# PowerCircuitry.net
KiCad netlist of a schematic drawn in Altium Designer
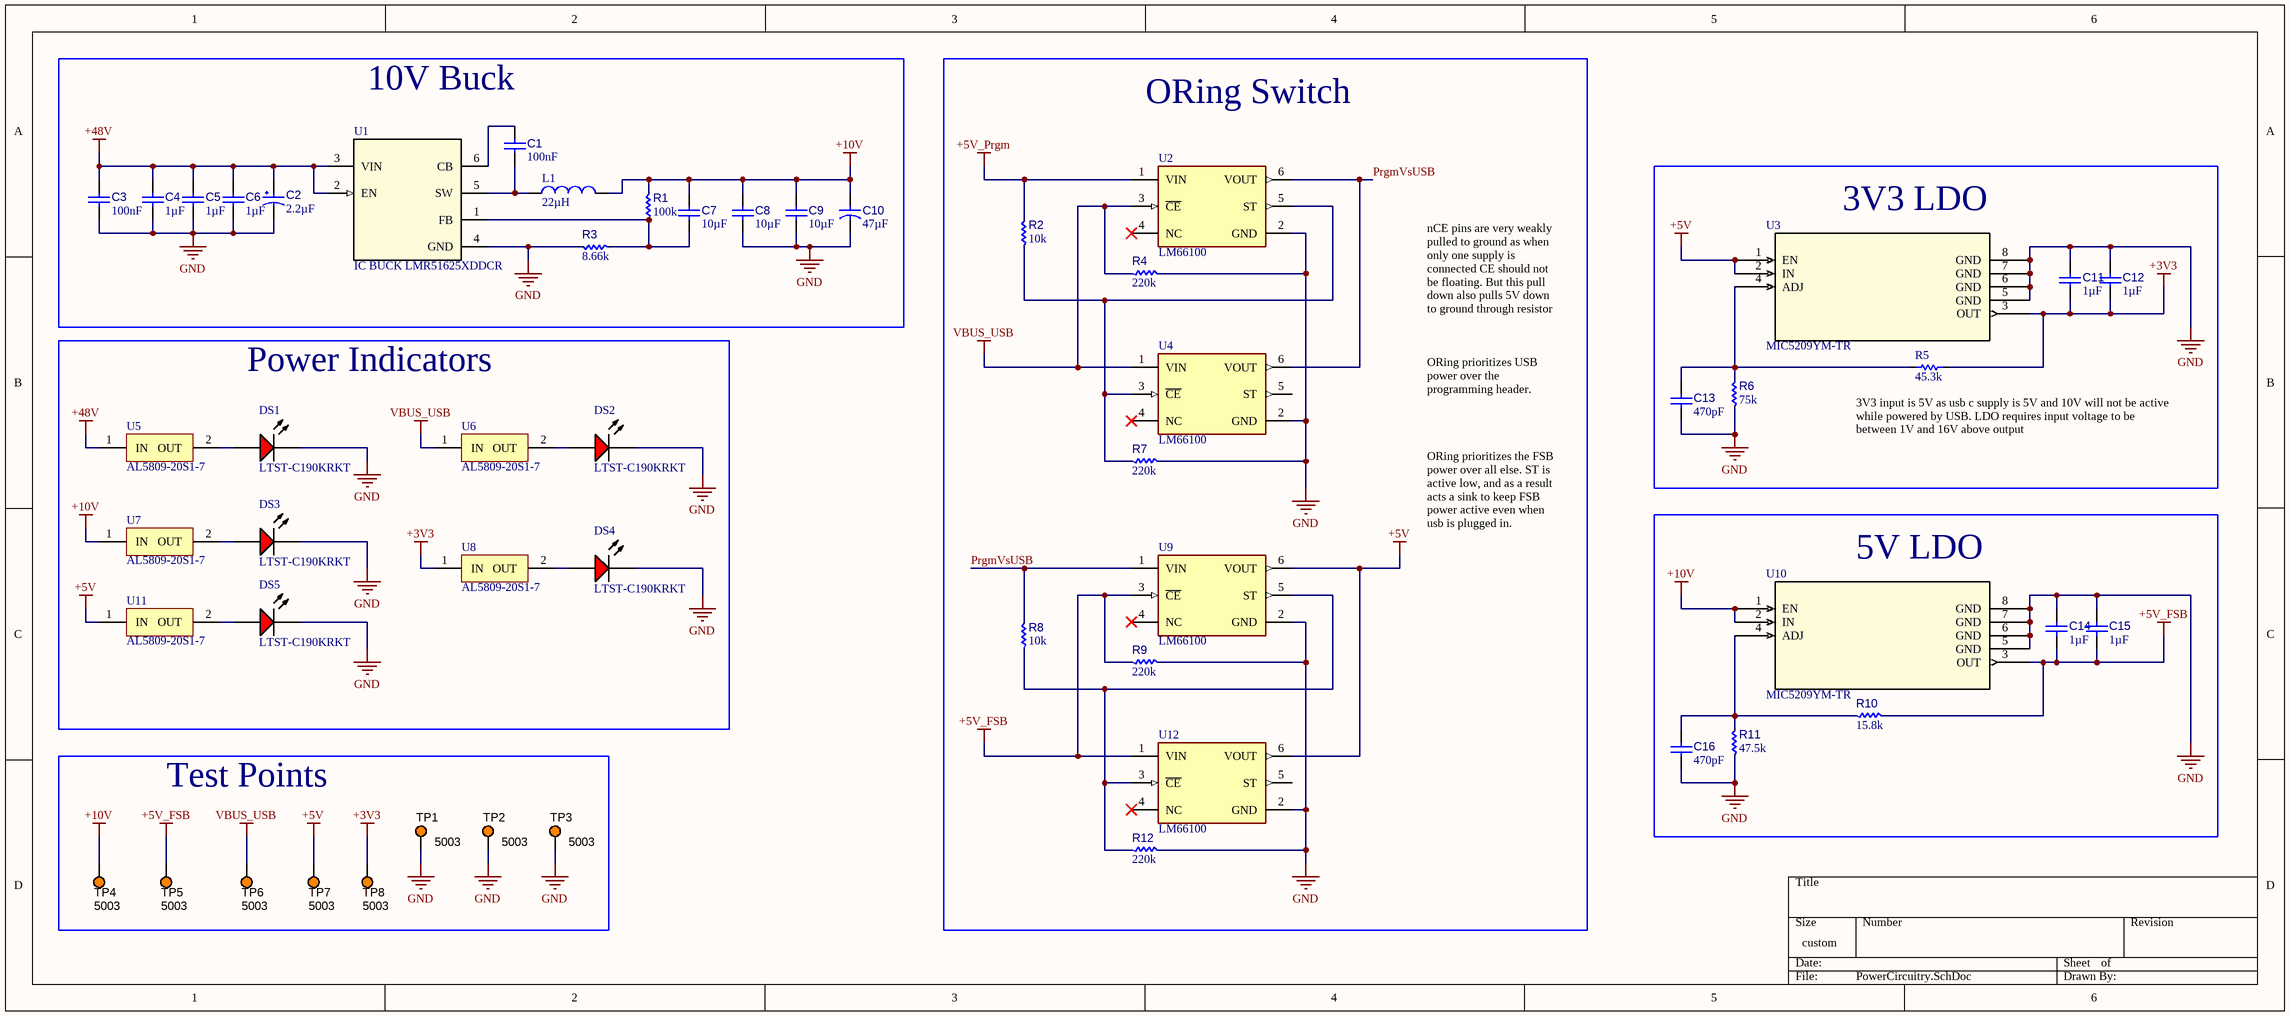
[diagram p0: PowerCircuitry.SchDoc]

(export (version "E")
  (design (tool "Eeschema 10.0.6"))
  (components
    (comp (ref "C1")
      (value "100nF")
      (footprint "CAPC0402(1005)60_L")
      (description "Chip Capacitor, 100nF +/-20%, 50V, 0402, Thickness 0.6 mm")
      (fields (field (name "TOLERANCE") "10%") (field (name "Comment") "Capacitor 100nF +/-20% 50V 0402"))
      (libsource (lib "University of Calgary - SOAR") (part "CAP-NP-2"))
    )
    (comp (ref "C2")
      (value "2.2µF")
      (footprint "CAPPR55-200-1100X500X1200")
      (fields
        (field (name "MANUFACTURER") "Panasonic")
        (field (name "TOLERANCE") "20%")
        (field (name "Comment") "CAP ELC 2.2uF 50V 20%")
      )
      (libsource (lib "University of Calgary - SOAR") (part "CAP-P-2"))
    )
    (comp (ref "C3")
      (value "100nF")
      (footprint "CL32B475KCVZW6E-Footprint-1")
      (description "C1210C104K1RACAUTO - Cap Ceramic 0.1uF 100V X7R 10% Pad SMD 1210 125C Automotive T/R")
      (fields (field (name "TOLERANCE") "10%") (field (name "Comment") "CAP CER 100nF 100V 10% 1210"))
      (libsource (lib "University of Calgary - SOAR") (part "CAP-NP-2"))
    )
    (comp (ref "C4")
      (value "1µF")
      (footprint "CAP_0603_LD")
      (fields
        (field (name "TOLERANCE") "10%")
        (field (name "VOLTAGE") "16V")
        (field (name "Comment") "CAP CER  1uF 50V X5R 0603")
      )
      (libsource (lib "University of Calgary - SOAR") (part "CAP-NP-2"))
    )
    (comp (ref "C5")
      (value "1µF")
      (footprint "CAP_0603_LD")
      (fields
        (field (name "TOLERANCE") "10%")
        (field (name "VOLTAGE") "16V")
        (field (name "Comment") "CAP CER  1uF 50V X5R 0603")
      )
      (libsource (lib "University of Calgary - SOAR") (part "CAP-NP-2"))
    )
    (comp (ref "C6")
      (value "1µF")
      (footprint "CAP_0603_LD")
      (fields
        (field (name "TOLERANCE") "10%")
        (field (name "VOLTAGE") "16V")
        (field (name "Comment") "CAP CER  1uF 50V X5R 0603")
      )
      (libsource (lib "University of Calgary - SOAR") (part "CAP-NP-2"))
    )
    (comp (ref "C7")
      (value "10µF")
      (footprint "CAPC0805(2012)145_L")
      (description "Chip Capacitor, 10µF +/-20%, 25V, 0805, Thickness 1.45 mm")
      (fields (field (name "TOLERANCE") "10%") (field (name "Comment") "Capacitor 10µF +/-20% 25V 0805"))
      (libsource (lib "University of Calgary - SOAR") (part "CAP-NP-2"))
    )
    (comp (ref "C8")
      (value "10µF")
      (footprint "CAPC0805(2012)145_L")
      (description "Chip Capacitor, 10µF +/-20%, 25V, 0805, Thickness 1.45 mm")
      (fields (field (name "TOLERANCE") "10%") (field (name "Comment") "Capacitor 10µF +/-20% 25V 0805"))
      (libsource (lib "University of Calgary - SOAR") (part "CAP-NP-2"))
    )
    (comp (ref "C9")
      (value "10µF")
      (footprint "CAPC0805(2012)145_L")
      (description "Chip Capacitor, 10µF +/-20%, 25V, 0805, Thickness 1.45 mm")
      (fields (field (name "TOLERANCE") "10%") (field (name "Comment") "Capacitor 10µF +/-20% 25V 0805"))
      (libsource (lib "University of Calgary - SOAR") (part "CAP-NP-2"))
    )
    (comp (ref "C10")
      (value "47µF")
      (footprint "FP-OS-CON-SMT-C6-MFG")
      (fields (field (name "Comment") "CAP ELC 47uF 25V 20% 2626"))
      (libsource (lib "") (part "CAP-NP-2_1"))
    )
    (comp (ref "C11")
      (value "1µF")
      (footprint "CAPC2013X145X50ML20T25")
      (description "Chip Capacitor, 1 uF, +/-10%, 25 V, 0805 (2012 Metric)")
      (fields (field (name "TOLERANCE") "10%") (field (name "Comment") "Capacitor 1 uF +/- 10% 25 V 0805"))
      (libsource (lib "University of Calgary - SOAR") (part "CAP-NP-2"))
    )
    (comp (ref "C12")
      (value "1µF")
      (footprint "CAPC2013X145X50ML20T25")
      (description "Chip Capacitor, 1 uF, +/-10%, 25 V, 0805 (2012 Metric)")
      (fields (field (name "TOLERANCE") "10%") (field (name "Comment") "Capacitor 1 uF +/- 10% 25 V 0805"))
      (libsource (lib "University of Calgary - SOAR") (part "CAP-NP-2"))
    )
    (comp (ref "C13")
      (value "470pF")
      (footprint "Copy of 0603")
      (fields (field (name "TOLERANCE") "2%") (field (name "Comment") "CAP 470pF FILM 16V 0603"))
      (libsource (lib "University of Calgary - SOAR") (part "470pF"))
    )
    (comp (ref "C14")
      (value "1µF")
      (footprint "CAPC2013X145X50ML20T25")
      (description "Chip Capacitor, 1 uF, +/-10%, 25 V, 0805 (2012 Metric)")
      (fields (field (name "TOLERANCE") "10%") (field (name "Comment") "Capacitor 1 uF +/- 10% 25 V 0805"))
      (libsource (lib "University of Calgary - SOAR") (part "CAP-NP-2"))
    )
    (comp (ref "C15")
      (value "1µF")
      (footprint "CAPC2013X145X50ML20T25")
      (description "Chip Capacitor, 1 uF, +/-10%, 25 V, 0805 (2012 Metric)")
      (fields (field (name "TOLERANCE") "10%") (field (name "Comment") "Capacitor 1 uF +/- 10% 25 V 0805"))
      (libsource (lib "University of Calgary - SOAR") (part "CAP-NP-2"))
    )
    (comp (ref "C16")
      (value "470pF")
      (footprint "Copy of 0603")
      (fields (field (name "TOLERANCE") "2%") (field (name "Comment") "CAP 470pF FILM 16V 0603"))
      (libsource (lib "University of Calgary - SOAR") (part "470pF"))
    )
    (comp (ref "DS1")
      (value "LTST-C190KRKT")
      (footprint "LTST-C191KRKT_V")
      (description "LED Uni-Color Red, 62.5 mW, 25 mA, -30 to 85 degC, 2-Pin SMD, RoHS, Tape and Reel")
      (fields (field (name "POWER") "75mW") (field (name "MANUFACTURER") "Lite-On"))
      (libsource (lib "University of Calgary - SOAR") (part "LED-RED-AK-2"))
    )
    (comp (ref "DS2")
      (value "LTST-C190KRKT")
      (footprint "LTST-C191KRKT_V")
      (description "LED Uni-Color Red, 62.5 mW, 25 mA, -30 to 85 degC, 2-Pin SMD, RoHS, Tape and Reel")
      (fields (field (name "POWER") "75mW") (field (name "MANUFACTURER") "Lite-On"))
      (libsource (lib "University of Calgary - SOAR") (part "LED-RED-AK-2"))
    )
    (comp (ref "DS3")
      (value "LTST-C190KRKT")
      (footprint "LTST-C191KRKT_V")
      (description "LED Uni-Color Red, 62.5 mW, 25 mA, -30 to 85 degC, 2-Pin SMD, RoHS, Tape and Reel")
      (fields (field (name "POWER") "75mW") (field (name "MANUFACTURER") "Lite-On"))
      (libsource (lib "University of Calgary - SOAR") (part "LED-RED-AK-2"))
    )
    (comp (ref "DS4")
      (value "LTST-C190KRKT")
      (footprint "LTST-C191KRKT_V")
      (description "LED Uni-Color Red, 62.5 mW, 25 mA, -30 to 85 degC, 2-Pin SMD, RoHS, Tape and Reel")
      (fields (field (name "POWER") "75mW") (field (name "MANUFACTURER") "Lite-On"))
      (libsource (lib "University of Calgary - SOAR") (part "LED-RED-AK-2"))
    )
    (comp (ref "DS5")
      (value "LTST-C190KRKT")
      (footprint "LTST-C191KRKT_V")
      (description "LED Uni-Color Red, 62.5 mW, 25 mA, -30 to 85 degC, 2-Pin SMD, RoHS, Tape and Reel")
      (fields (field (name "POWER") "75mW") (field (name "MANUFACTURER") "Lite-On"))
      (libsource (lib "University of Calgary - SOAR") (part "LED-RED-AK-2"))
    )
    (comp (ref "L1")
      (value "22µH")
      (footprint "IND WIR 22uH 3.5A 20%-Footprint-1")
      (fields (field (name "TOLERANCE") "20%") (field (name "Comment") "IND WIR 22uH 3.5A 20%"))
      (libsource (lib "University of Calgary - SOAR") (part "22uH"))
    )
    (comp (ref "R1")
      (value "100k")
      (footprint "RESC2013X70X40ML20T20")
      (description "Chip Resistor, 100 KOhm, +/- 1%, 0.125 W, -55 to 155 degC, 0805 (2012 Metric)")
      (fields (field (name "POWER") "125mW") (field (name "TOLERANCE") "1%"))
      (libsource (lib "University of Calgary - SOAR") (part "RES-2"))
    )
    (comp (ref "R2")
      (value "10k")
      (footprint "RESC1005X40X25ML05T05")
      (description "Chip Resistor, 10 KOhm, +/- 1%, 0.1 W, -55 to 155 degC, 0402 (1005 Metric)")
      (fields (field (name "POWER") "100mW") (field (name "TOLERANCE") "1%"))
      (libsource (lib "University of Calgary - SOAR") (part "RES-2"))
    )
    (comp (ref "R3")
      (value "8.66k")
      (footprint "RES 8.66K OHM 1% 1_8W 0805-Footprint-1")
      (fields (field (name "TOLERANCE") "1%") (field (name "Comment") "RES 8.66K OHM 1% 1/8W 0805"))
      (libsource (lib "University of Calgary - SOAR") (part "8.66k"))
    )
    (comp (ref "R4")
      (value "220k")
      (footprint "FP-CRGCQ0603-IPC_A")
      (description "Res Thick Film 0603 220K Ohm 1% 0.1W(1/10W) ±100ppm/C Pad SMD Automotive T/R")
      (fields (field (name "TOLERANCE") "1%") (field (name "Comment") "RMCF0603FT220K"))
      (libsource (lib "University of Calgary - SOAR") (part "RES-2"))
    )
    (comp (ref "R5")
      (value "45.3k")
      (footprint "0603")
      (fields
        (field (name "POWER") "150mW")
        (field (name "TOLERANCE") "0.1%")
        (field (name "Comment") "RES 43.5kR 0.15W 0.1% 0603")
      )
      (libsource (lib "University of Calgary - SOAR") (part "RC0603FR-071KL"))
    )
    (comp (ref "R6")
      (value "75k")
      (footprint "RES 75k 1% 0.1W 0603-Footprint-1")
      (fields
        (field (name "TOLERANCE") "1%")
        (field (name "POWER") "100mW")
        (field (name "Comment") "RES 75k 1% 0.1W 0603")
      )
      (libsource (lib "University of Calgary - SOAR") (part "RES-2"))
    )
    (comp (ref "R7")
      (value "220k")
      (footprint "FP-CRGCQ0603-IPC_A")
      (description "Res Thick Film 0603 220K Ohm 1% 0.1W(1/10W) ±100ppm/C Pad SMD Automotive T/R")
      (fields (field (name "TOLERANCE") "1%") (field (name "Comment") "RMCF0603FT220K"))
      (libsource (lib "University of Calgary - SOAR") (part "RES-2"))
    )
    (comp (ref "R8")
      (value "10k")
      (footprint "RESC1005X40X25ML05T05")
      (description "Chip Resistor, 10 KOhm, +/- 1%, 0.1 W, -55 to 155 degC, 0402 (1005 Metric)")
      (fields (field (name "POWER") "100mW") (field (name "TOLERANCE") "1%"))
      (libsource (lib "University of Calgary - SOAR") (part "RES-2"))
    )
    (comp (ref "R9")
      (value "220k")
      (footprint "FP-CRGCQ0603-IPC_A")
      (description "Res Thick Film 0603 220K Ohm 1% 0.1W(1/10W) ±100ppm/C Pad SMD Automotive T/R")
      (fields (field (name "TOLERANCE") "1%") (field (name "Comment") "RMCF0603FT220K"))
      (libsource (lib "University of Calgary - SOAR") (part "RES-2"))
    )
    (comp (ref "R10")
      (value "15.8k")
      (footprint "RES 15.8k 1% 0.1W 0603-Footprint-1")
      (fields
        (field (name "POWER") "100mW")
        (field (name "TOLERANCE") "1%")
        (field (name "Comment") "RES 15.8k 1% 0.1W 0603")
      )
      (libsource (lib "University of Calgary - SOAR") (part "RES-2"))
    )
    (comp (ref "R11")
      (value "47.5k")
      (footprint "RES 47.5k 1% 0.1W 0603-Footprint-1")
      (fields
        (field (name "POWER") "100mW")
        (field (name "TOLERANCE") "1%")
        (field (name "Comment") "RES 47.5k 1% 0.1W 0603")
      )
      (libsource (lib "University of Calgary - SOAR") (part "RES-2"))
    )
    (comp (ref "R12")
      (value "220k")
      (footprint "FP-CRGCQ0603-IPC_A")
      (description "Res Thick Film 0603 220K Ohm 1% 0.1W(1/10W) ±100ppm/C Pad SMD Automotive T/R")
      (fields (field (name "TOLERANCE") "1%") (field (name "Comment") "RMCF0603FT220K"))
      (libsource (lib "University of Calgary - SOAR") (part "RES-2"))
    )
    (comp (ref "TP1")
      (value "5003")
      (footprint "KSTN-5003")
      (description "Test Point, Orange, Height 4.6 mm, Tail Length 3 mm, 1-Pin THD, RoHS")
      (fields (field (name "MANUFACTURER") "Keystone"))
      (libsource (lib "University of Calgary - SOAR") (part "TESTPOINT_ORANGE"))
    )
    (comp (ref "TP2")
      (value "5003")
      (footprint "KSTN-5003")
      (description "Test Point, Orange, Height 4.6 mm, Tail Length 3 mm, 1-Pin THD, RoHS")
      (fields (field (name "MANUFACTURER") "Keystone"))
      (libsource (lib "University of Calgary - SOAR") (part "TESTPOINT_ORANGE"))
    )
    (comp (ref "TP3")
      (value "5003")
      (footprint "KSTN-5003")
      (description "Test Point, Orange, Height 4.6 mm, Tail Length 3 mm, 1-Pin THD, RoHS")
      (fields (field (name "MANUFACTURER") "Keystone"))
      (libsource (lib "University of Calgary - SOAR") (part "TESTPOINT_ORANGE"))
    )
    (comp (ref "TP4")
      (value "5003")
      (footprint "KSTN-5003")
      (description "Test Point, Orange, Height 4.6 mm, Tail Length 3 mm, 1-Pin THD, RoHS")
      (fields (field (name "MANUFACTURER") "Keystone"))
      (libsource (lib "University of Calgary - SOAR") (part "TESTPOINT_ORANGE"))
    )
    (comp (ref "TP5")
      (value "5003")
      (footprint "KSTN-5003")
      (description "Test Point, Orange, Height 4.6 mm, Tail Length 3 mm, 1-Pin THD, RoHS")
      (fields (field (name "MANUFACTURER") "Keystone"))
      (libsource (lib "University of Calgary - SOAR") (part "TESTPOINT_ORANGE"))
    )
    (comp (ref "TP6")
      (value "5003")
      (footprint "KSTN-5003")
      (description "Test Point, Orange, Height 4.6 mm, Tail Length 3 mm, 1-Pin THD, RoHS")
      (fields (field (name "MANUFACTURER") "Keystone"))
      (libsource (lib "University of Calgary - SOAR") (part "TESTPOINT_ORANGE"))
    )
    (comp (ref "TP7")
      (value "5003")
      (footprint "KSTN-5003")
      (description "Test Point, Orange, Height 4.6 mm, Tail Length 3 mm, 1-Pin THD, RoHS")
      (fields (field (name "MANUFACTURER") "Keystone"))
      (libsource (lib "University of Calgary - SOAR") (part "TESTPOINT_ORANGE"))
    )
    (comp (ref "TP8")
      (value "5003")
      (footprint "KSTN-5003")
      (description "Test Point, Orange, Height 4.6 mm, Tail Length 3 mm, 1-Pin THD, RoHS")
      (fields (field (name "MANUFACTURER") "Keystone"))
      (libsource (lib "University of Calgary - SOAR") (part "TESTPOINT_ORANGE"))
    )
    (comp (ref "U1")
      (value "IC BUCK LMR51625XDDCR")
      (footprint "IC BUCK LMR51625XDDCR-Footprint-1")
      (libsource (lib "University of Calgary - SOAR") (part "IC BUCK LMR51625XDDCR"))
    )
    (comp (ref "U2")
      (value "LM66100")
      (footprint "FP-DCK0006A-MFG")
      (description "1.5-V to 5.5-V, 1.5-A, 0.5-µA IQ ideal diode with integrated FET 6-SC70 -40 to 105")
      (libsource (lib "University of Calgary - SOAR") (part "3595dc506fef48fc1df3095330a4feb"))
    )
    (comp (ref "U3")
      (value "MIC5209YM-TR")
      (footprint "MIC5209YM-TR-Footprint-1")
      (description "IC REG LIN POS ADJ 500MA 8SOIC")
      (libsource (lib "University of Calgary - SOAR") (part "MIC5209YM-TR-Symbol-1"))
    )
    (comp (ref "U4")
      (value "LM66100")
      (footprint "FP-DCK0006A-MFG")
      (description "1.5-V to 5.5-V, 1.5-A, 0.5-µA IQ ideal diode with integrated FET 6-SC70 -40 to 105")
      (libsource (lib "University of Calgary - SOAR") (part "3595dc506fef48fc1df3095330a4feb"))
    )
    (comp (ref "U5")
      (value "AL5809-20S1-7")
      (footprint "DIOD-SOD123-A_V")
      (description "Led Driver, Cc/Linear, -40 To 125Deg C Rohs Compliant: Yes")
      (libsource (lib "University of Calgary - SOAR") (part "DIOD-AL5809-2"))
    )
    (comp (ref "U6")
      (value "AL5809-20S1-7")
      (footprint "DIOD-SOD123-A_V")
      (description "Led Driver, Cc/Linear, -40 To 125Deg C Rohs Compliant: Yes")
      (libsource (lib "University of Calgary - SOAR") (part "DIOD-AL5809-2"))
    )
    (comp (ref "U7")
      (value "AL5809-20S1-7")
      (footprint "DIOD-SOD123-A_V")
      (description "Led Driver, Cc/Linear, -40 To 125Deg C Rohs Compliant: Yes")
      (libsource (lib "University of Calgary - SOAR") (part "DIOD-AL5809-2"))
    )
    (comp (ref "U8")
      (value "AL5809-20S1-7")
      (footprint "DIOD-SOD123-A_V")
      (description "Led Driver, Cc/Linear, -40 To 125Deg C Rohs Compliant: Yes")
      (libsource (lib "University of Calgary - SOAR") (part "DIOD-AL5809-2"))
    )
    (comp (ref "U9")
      (value "LM66100")
      (footprint "FP-DCK0006A-MFG")
      (description "1.5-V to 5.5-V, 1.5-A, 0.5-µA IQ ideal diode with integrated FET 6-SC70 -40 to 105")
      (libsource (lib "University of Calgary - SOAR") (part "3595dc506fef48fc1df3095330a4feb"))
    )
    (comp (ref "U10")
      (value "MIC5209YM-TR")
      (footprint "MIC5209YM-TR-Footprint-1")
      (description "IC REG LIN POS ADJ 500MA 8SOIC")
      (libsource (lib "University of Calgary - SOAR") (part "MIC5209YM-TR-Symbol-1"))
    )
    (comp (ref "U11")
      (value "AL5809-20S1-7")
      (footprint "DIOD-SOD123-A_V")
      (description "Led Driver, Cc/Linear, -40 To 125Deg C Rohs Compliant: Yes")
      (libsource (lib "University of Calgary - SOAR") (part "DIOD-AL5809-2"))
    )
    (comp (ref "U12")
      (value "LM66100")
      (footprint "FP-DCK0006A-MFG")
      (description "1.5-V to 5.5-V, 1.5-A, 0.5-µA IQ ideal diode with integrated FET 6-SC70 -40 to 105")
      (libsource (lib "University of Calgary - SOAR") (part "3595dc506fef48fc1df3095330a4feb"))
    )
  )
  (nets
    (net (code "1") (name "+3V3") (class "Default")
      (node (ref "C11") (pin "1") (pinfunction "1_1") (pintype "passive"))
      (node (ref "C12") (pin "1") (pinfunction "1_1") (pintype "passive"))
      (node (ref "R5") (pin "2") (pinfunction "2_2") (pintype "passive"))
      (node (ref "TP8") (pin "1") (pinfunction "1_1") (pintype "passive"))
      (node (ref "U3") (pin "3") (pinfunction "OUT_3") (pintype "output"))
      (node (ref "U8") (pin "1") (pinfunction "IN_1") (pintype "passive"))
    )
    (net (code "2") (name "+5V") (class "Default")
      (node (ref "TP7") (pin "1") (pinfunction "1_1") (pintype "passive"))
      (node (ref "U11") (pin "1") (pinfunction "IN_1") (pintype "passive"))
      (node (ref "U12") (pin "6") (pinfunction "VOUT_6") (pintype "output"))
      (node (ref "U3") (pin "1") (pinfunction "EN_1") (pintype "input"))
      (node (ref "U3") (pin "2") (pinfunction "IN_2") (pintype "input"))
      (node (ref "U9") (pin "6") (pinfunction "VOUT_6") (pintype "output"))
    )
    (net (code "3") (name "+5V_FSB") (class "Default")
      (node (ref "C14") (pin "1") (pinfunction "1_1") (pintype "passive"))
      (node (ref "C15") (pin "1") (pinfunction "1_1") (pintype "passive"))
      (node (ref "R10") (pin "2") (pinfunction "2_2") (pintype "passive"))
      (node (ref "R9") (pin "1") (pinfunction "1_1") (pintype "passive"))
      (node (ref "TP5") (pin "1") (pinfunction "1_1") (pintype "passive"))
      (node (ref "U10") (pin "3") (pinfunction "OUT_3") (pintype "output"))
      (node (ref "U12") (pin "1") (pinfunction "VIN_1") (pintype "power_in"))
      (node (ref "U9") (pin "3") (pinfunction "~{CE}_3") (pintype "input"))
    )
    (net (code "4") (name "+5V_Prgm") (class "Default")
      (node (ref "R2") (pin "2") (pinfunction "2_2") (pintype "passive"))
      (node (ref "U2") (pin "1") (pinfunction "VIN_1") (pintype "power_in"))
    )
    (net (code "5") (name "+10V") (class "Default")
      (node (ref "C10") (pin "2") (pinfunction "2_2") (pintype "passive"))
      (node (ref "C7") (pin "2") (pinfunction "2_2") (pintype "passive"))
      (node (ref "C8") (pin "2") (pinfunction "2_2") (pintype "passive"))
      (node (ref "C9") (pin "2") (pinfunction "2_2") (pintype "passive"))
      (node (ref "L1") (pin "2") (pinfunction "2_2") (pintype "passive"))
      (node (ref "R1") (pin "2") (pinfunction "2_2") (pintype "passive"))
      (node (ref "TP4") (pin "1") (pinfunction "1_1") (pintype "passive"))
      (node (ref "U10") (pin "1") (pinfunction "EN_1") (pintype "input"))
      (node (ref "U10") (pin "2") (pinfunction "IN_2") (pintype "input"))
      (node (ref "U7") (pin "1") (pinfunction "IN_1") (pintype "passive"))
    )
    (net (code "6") (name "+48V") (class "Default")
      (node (ref "C2") (pin "1") (pinfunction "1_1") (pintype "passive"))
      (node (ref "C3") (pin "2") (pinfunction "2_2") (pintype "passive"))
      (node (ref "C4") (pin "2") (pinfunction "2_2") (pintype "passive"))
      (node (ref "C5") (pin "2") (pinfunction "2_2") (pintype "passive"))
      (node (ref "C6") (pin "2") (pinfunction "2_2") (pintype "passive"))
      (node (ref "U1") (pin "2") (pinfunction "EN_2") (pintype "input"))
      (node (ref "U1") (pin "3") (pinfunction "VIN_3") (pintype "power_in"))
      (node (ref "U5") (pin "1") (pinfunction "IN_1") (pintype "passive"))
    )
    (net (code "7") (name "/PrgmVsUSB") (class "Default")
      (node (ref "R8") (pin "2") (pinfunction "2_2") (pintype "passive"))
      (node (ref "U2") (pin "6") (pinfunction "VOUT_6") (pintype "output"))
      (node (ref "U4") (pin "6") (pinfunction "VOUT_6") (pintype "output"))
      (node (ref "U9") (pin "1") (pinfunction "VIN_1") (pintype "power_in"))
    )
    (net (code "8") (name "GND") (class "Default")
      (node (ref "C10") (pin "1") (pinfunction "1_1") (pintype "passive"))
      (node (ref "C11") (pin "2") (pinfunction "2_2") (pintype "passive"))
      (node (ref "C12") (pin "2") (pinfunction "2_2") (pintype "passive"))
      (node (ref "C13") (pin "1") (pinfunction "1_1") (pintype "passive"))
      (node (ref "C14") (pin "2") (pinfunction "2_2") (pintype "passive"))
      (node (ref "C15") (pin "2") (pinfunction "2_2") (pintype "passive"))
      (node (ref "C16") (pin "1") (pinfunction "1_1") (pintype "passive"))
      (node (ref "C2") (pin "2") (pinfunction "2_2") (pintype "passive"))
      (node (ref "C3") (pin "1") (pinfunction "1_1") (pintype "passive"))
      (node (ref "C4") (pin "1") (pinfunction "1_1") (pintype "passive"))
      (node (ref "C5") (pin "1") (pinfunction "1_1") (pintype "passive"))
      (node (ref "C6") (pin "1") (pinfunction "1_1") (pintype "passive"))
      (node (ref "C8") (pin "1") (pinfunction "1_1") (pintype "passive"))
      (node (ref "C9") (pin "1") (pinfunction "1_1") (pintype "passive"))
      (node (ref "DS1") (pin "2") (pinfunction "K_2") (pintype "passive"))
      (node (ref "DS2") (pin "2") (pinfunction "K_2") (pintype "passive"))
      (node (ref "DS3") (pin "2") (pinfunction "K_2") (pintype "passive"))
      (node (ref "DS4") (pin "2") (pinfunction "K_2") (pintype "passive"))
      (node (ref "DS5") (pin "2") (pinfunction "K_2") (pintype "passive"))
      (node (ref "R11") (pin "1") (pinfunction "1_1") (pintype "passive"))
      (node (ref "R12") (pin "2") (pinfunction "2_2") (pintype "passive"))
      (node (ref "R3") (pin "2") (pinfunction "2_2") (pintype "passive"))
      (node (ref "R4") (pin "2") (pinfunction "2_2") (pintype "passive"))
      (node (ref "R6") (pin "1") (pinfunction "1_1") (pintype "passive"))
      (node (ref "R7") (pin "2") (pinfunction "2_2") (pintype "passive"))
      (node (ref "R9") (pin "2") (pinfunction "2_2") (pintype "passive"))
      (node (ref "TP1") (pin "1") (pinfunction "1_1") (pintype "passive"))
      (node (ref "TP2") (pin "1") (pinfunction "1_1") (pintype "passive"))
      (node (ref "TP3") (pin "1") (pinfunction "1_1") (pintype "passive"))
      (node (ref "U1") (pin "4") (pinfunction "GND_4") (pintype "power_in"))
      (node (ref "U10") (pin "5") (pinfunction "GND_5") (pintype "power_in"))
      (node (ref "U10") (pin "6") (pinfunction "GND_6") (pintype "power_in"))
      (node (ref "U10") (pin "7") (pinfunction "GND_7") (pintype "power_in"))
      (node (ref "U10") (pin "8") (pinfunction "GND_8") (pintype "power_in"))
      (node (ref "U12") (pin "2") (pinfunction "GND_2") (pintype "power_in"))
      (node (ref "U2") (pin "2") (pinfunction "GND_2") (pintype "power_in"))
      (node (ref "U3") (pin "5") (pinfunction "GND_5") (pintype "power_in"))
      (node (ref "U3") (pin "6") (pinfunction "GND_6") (pintype "power_in"))
      (node (ref "U3") (pin "7") (pinfunction "GND_7") (pintype "power_in"))
      (node (ref "U3") (pin "8") (pinfunction "GND_8") (pintype "power_in"))
      (node (ref "U4") (pin "2") (pinfunction "GND_2") (pintype "power_in"))
      (node (ref "U9") (pin "2") (pinfunction "GND_2") (pintype "power_in"))
    )
    (net (code "9") (name "Net-(DS1-A)") (class "Default")
      (node (ref "DS1") (pin "1") (pinfunction "A_1") (pintype "passive"))
      (node (ref "U5") (pin "2") (pinfunction "OUT_2") (pintype "passive"))
    )
    (net (code "10") (name "Net-(DS2-A)") (class "Default")
      (node (ref "DS2") (pin "1") (pinfunction "A_1") (pintype "passive"))
      (node (ref "U6") (pin "2") (pinfunction "OUT_2") (pintype "passive"))
    )
    (net (code "11") (name "Net-(DS3-A)") (class "Default")
      (node (ref "DS3") (pin "1") (pinfunction "A_1") (pintype "passive"))
      (node (ref "U7") (pin "2") (pinfunction "OUT_2") (pintype "passive"))
    )
    (net (code "12") (name "Net-(DS4-A)") (class "Default")
      (node (ref "DS4") (pin "1") (pinfunction "A_1") (pintype "passive"))
      (node (ref "U8") (pin "2") (pinfunction "OUT_2") (pintype "passive"))
    )
    (net (code "13") (name "Net-(DS5-A)") (class "Default")
      (node (ref "DS5") (pin "1") (pinfunction "A_1") (pintype "passive"))
      (node (ref "U11") (pin "2") (pinfunction "OUT_2") (pintype "passive"))
    )
    (net (code "14") (name "Net-(U1-CB)") (class "Default")
      (node (ref "C1") (pin "2") (pinfunction "2_2") (pintype "passive"))
      (node (ref "U1") (pin "6") (pinfunction "CB_6") (pintype "passive"))
    )
    (net (code "15") (name "Net-(U1-FB)") (class "Default")
      (node (ref "C7") (pin "1") (pinfunction "1_1") (pintype "passive"))
      (node (ref "R1") (pin "1") (pinfunction "1_1") (pintype "passive"))
      (node (ref "R3") (pin "1") (pinfunction "1_1") (pintype "passive"))
      (node (ref "U1") (pin "1") (pinfunction "FB_1") (pintype "passive"))
    )
    (net (code "16") (name "Net-(U1-SW)") (class "Default")
      (node (ref "C1") (pin "1") (pinfunction "1_1") (pintype "passive"))
      (node (ref "L1") (pin "1") (pinfunction "1_1") (pintype "passive"))
      (node (ref "U1") (pin "5") (pinfunction "SW_5") (pintype "passive"))
    )
    (net (code "17") (name "Net-(U2-ST)") (class "Default")
      (node (ref "R2") (pin "1") (pinfunction "1_1") (pintype "passive"))
      (node (ref "R7") (pin "1") (pinfunction "1_1") (pintype "passive"))
      (node (ref "U2") (pin "5") (pinfunction "ST_5") (pintype "output"))
      (node (ref "U4") (pin "3") (pinfunction "~{CE}_3") (pintype "input"))
    )
    (net (code "18") (name "Net-(U3-ADJ)") (class "Default")
      (node (ref "C13") (pin "2") (pinfunction "2_2") (pintype "passive"))
      (node (ref "R5") (pin "1") (pinfunction "1_1") (pintype "passive"))
      (node (ref "R6") (pin "2") (pinfunction "2_2") (pintype "passive"))
      (node (ref "U3") (pin "4") (pinfunction "ADJ_4") (pintype "input"))
    )
    (net (code "19") (name "Net-(U10-ADJ)") (class "Default")
      (node (ref "C16") (pin "2") (pinfunction "2_2") (pintype "passive"))
      (node (ref "R10") (pin "1") (pinfunction "1_1") (pintype "passive"))
      (node (ref "R11") (pin "2") (pinfunction "2_2") (pintype "passive"))
      (node (ref "U10") (pin "4") (pinfunction "ADJ_4") (pintype "input"))
    )
    (net (code "20") (name "Net-(U12-~{CE})") (class "Default")
      (node (ref "R12") (pin "1") (pinfunction "1_1") (pintype "passive"))
      (node (ref "R8") (pin "1") (pinfunction "1_1") (pintype "passive"))
      (node (ref "U12") (pin "3") (pinfunction "~{CE}_3") (pintype "input"))
      (node (ref "U9") (pin "5") (pinfunction "ST_5") (pintype "output"))
    )
    (net (code "21") (name "VBUS_USB") (class "Default")
      (node (ref "R4") (pin "1") (pinfunction "1_1") (pintype "passive"))
      (node (ref "TP6") (pin "1") (pinfunction "1_1") (pintype "passive"))
      (node (ref "U2") (pin "3") (pinfunction "~{CE}_3") (pintype "input"))
      (node (ref "U4") (pin "1") (pinfunction "VIN_1") (pintype "power_in"))
      (node (ref "U6") (pin "1") (pinfunction "IN_1") (pintype "passive"))
    )
    (net (code "22") (name "unconnected-(U2-NC-Pad4)") (class "Default")
      (node (ref "U2") (pin "4") (pinfunction "NC_4") (pintype "passive+no_connect"))
    )
    (net (code "23") (name "unconnected-(U4-NC-Pad4)") (class "Default")
      (node (ref "U4") (pin "4") (pinfunction "NC_4") (pintype "passive+no_connect"))
    )
    (net (code "24") (name "unconnected-(U4-ST-Pad5)") (class "Default")
      (node (ref "U4") (pin "5") (pinfunction "ST_5") (pintype "output"))
    )
    (net (code "25") (name "unconnected-(U9-NC-Pad4)") (class "Default")
      (node (ref "U9") (pin "4") (pinfunction "NC_4") (pintype "passive+no_connect"))
    )
    (net (code "26") (name "unconnected-(U12-NC-Pad4)") (class "Default")
      (node (ref "U12") (pin "4") (pinfunction "NC_4") (pintype "passive+no_connect"))
    )
    (net (code "27") (name "unconnected-(U12-ST-Pad5)") (class "Default")
      (node (ref "U12") (pin "5") (pinfunction "ST_5") (pintype "output"))
    )
  )
)
